# 06-multimodal-analogfrontend-PPG.net
KiCad netlist of a schematic drawn in Altium Designer
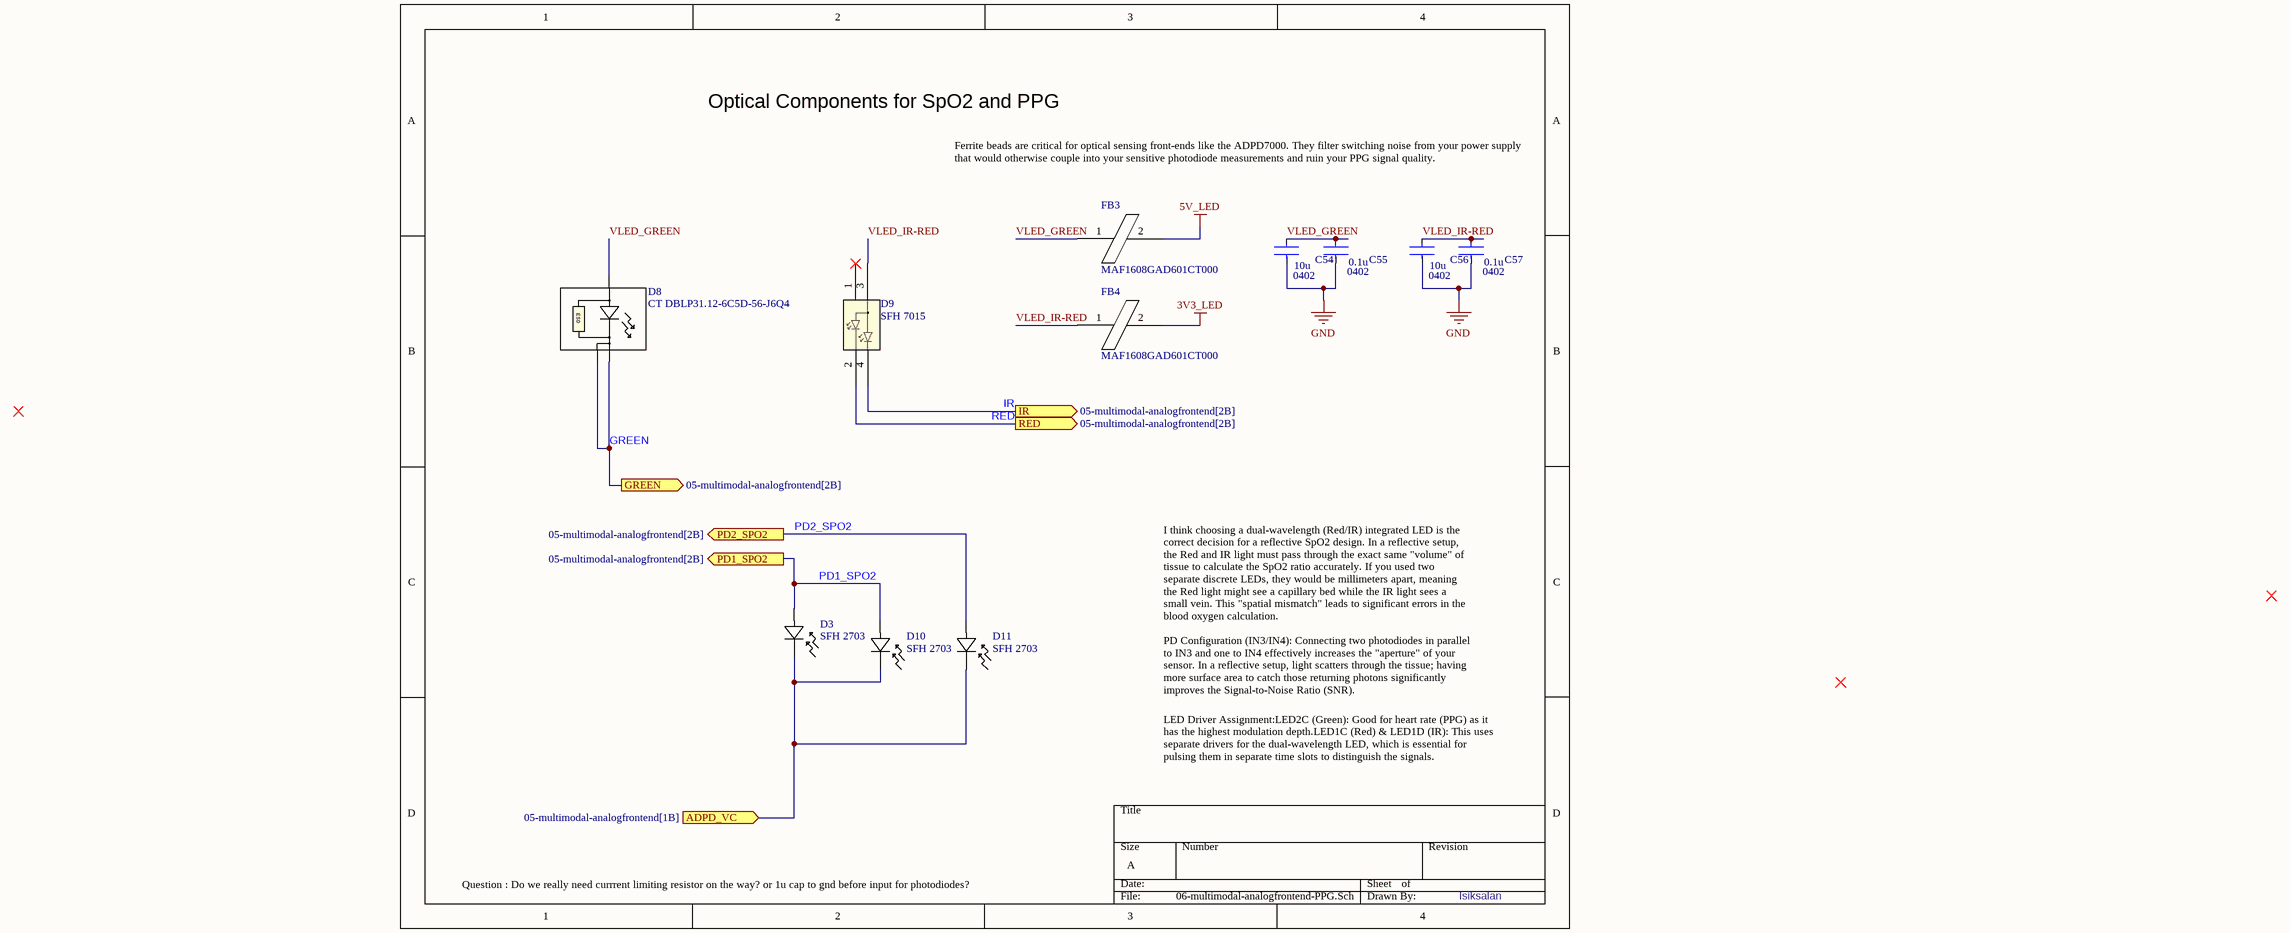
[diagram p0: 06-multimodal-analogfrontend-PPG.SchDoc]

(export (version "E")
  (design (tool "Eeschema 10.0.6"))
  (components
    (comp (ref "C54")
      (value "0402W106M6R3HI")
      (footprint "CAPTDK0402")
      (description "CAP SMD,0402,X5R,10UF,20%,6.3V")
      (libsource (lib "multimodal") (part "0402W106M6R3HI"))
    )
    (comp (ref "C55")
      (value "C1005X7R1H104K050BB")
      (footprint "CAPTDK0402")
      (description "CAP CER 0.1UF 50V X7R 0402")
      (libsource (lib "multimodal") (part "C1005X7R1H104K050BB"))
    )
    (comp (ref "C56")
      (value "0402W106M6R3HI")
      (footprint "CAPTDK0402")
      (description "CAP SMD,0402,X5R,10UF,20%,6.3V")
      (libsource (lib "multimodal") (part "0402W106M6R3HI"))
    )
    (comp (ref "C57")
      (value "C1005X7R1H104K050BB")
      (footprint "CAPTDK0402")
      (description "CAP CER 0.1UF 50V X7R 0402")
      (libsource (lib "multimodal") (part "C1005X7R1H104K050BB"))
    )
    (comp (ref "D3")
      (value "SFH 2703")
      (footprint "LED_SFH 2703_OSR")
      (description "SENSOR PHOTODIODE 940NM 2SMD")
      (fields (field (name "COPYRIGHT") "Copyright (C) 2025 Ultra Librarian. All rights reserved."))
      (libsource (lib "multimodal") (part "SFH 2703"))
    )
    (comp (ref "D8")
      (value "CT DBLP31.12-6C5D-56-J6Q4")
      (footprint "CT DBLP31.12-6C5D-56-J6Q4_OSR")
      (description "LED GREEN CLEAR SMD Green 536nm LED Indication - Discrete 2.3V 3-SMD, No Lead")
      (fields (field (name "COPYRIGHT") "Copyright (C) 2025 Ultra Librarian. All rights reserved."))
      (libsource (lib "multimodal") (part "CT DBLP31.12-6C5D-56-J6Q4"))
    )
    (comp (ref "D9")
      (value "SFH 7015")
      (footprint "SFH 7015_OSR")
      (description "Multi-Color LEDs Red / IR LED 655nm / 940nm")
      (fields (field (name "COPYRIGHT") "Copyright (C) 2026 Ultra Librarian. All rights reserved."))
      (libsource (lib "multimodal") (part "SFH 7015"))
    )
    (comp (ref "D10")
      (value "SFH 2703")
      (footprint "LED_SFH 2703_OSR")
      (description "SENSOR PHOTODIODE 940NM 2SMD")
      (fields (field (name "COPYRIGHT") "Copyright (C) 2025 Ultra Librarian. All rights reserved."))
      (libsource (lib "multimodal") (part "SFH 2703"))
    )
    (comp (ref "D11")
      (value "SFH 2703")
      (footprint "LED_SFH 2703_OSR")
      (description "SENSOR PHOTODIODE 940NM 2SMD")
      (fields (field (name "COPYRIGHT") "Copyright (C) 2025 Ultra Librarian. All rights reserved."))
      (libsource (lib "multimodal") (part "SFH 2703"))
    )
    (comp (ref "FB3")
      (value "MAF1608GAD601CT000")
      (footprint "INDMURT0603")
      (description "FERRITE BEAD 120 OHM 0603 1LN")
      (libsource (lib "multimodal") (part "MAF1608GAD601CT000"))
    )
    (comp (ref "FB4")
      (value "MAF1608GAD601CT000")
      (footprint "INDMURT0603")
      (description "FERRITE BEAD 120 OHM 0603 1LN")
      (libsource (lib "multimodal") (part "MAF1608GAD601CT000"))
    )
  )
  (nets
    (net (code "2") (name "/ADPD_VC") (class "Default")
      (node (ref "D10") (pin "1") (pinfunction "1_1") (pintype "passive"))
      (node (ref "D11") (pin "1") (pinfunction "1_1") (pintype "passive"))
      (node (ref "D3") (pin "1") (pinfunction "1_1") (pintype "passive"))
    )
    (net (code "3") (name "/GREEN") (class "Default")
      (node (ref "D8") (pin "1") (pinfunction "1_1") (pintype "passive"))
      (node (ref "D8") (pin "3") (pinfunction "3_3") (pintype "passive"))
    )
    (net (code "4") (name "/IR") (class "Default")
      (node (ref "D9") (pin "4") (pinfunction "4_4") (pintype "passive"))
    )
    (net (code "5") (name "/PD1_SPO2") (class "Default")
      (node (ref "D10") (pin "2") (pinfunction "2_2") (pintype "passive"))
      (node (ref "D3") (pin "2") (pinfunction "2_2") (pintype "passive"))
    )
    (net (code "6") (name "/PD2_SPO2") (class "Default")
      (node (ref "D11") (pin "2") (pinfunction "2_2") (pintype "passive"))
    )
    (net (code "7") (name "/RED") (class "Default")
      (node (ref "D9") (pin "2") (pinfunction "2_2") (pintype "passive"))
    )
    (net (code "8") (name "/VLED_GREEN") (class "Default")
      (node (ref "C54") (pin "1") (pinfunction "1_1") (pintype "passive"))
      (node (ref "C55") (pin "1") (pinfunction "1_1") (pintype "passive"))
      (node (ref "D8") (pin "2") (pinfunction "2_2") (pintype "passive"))
      (node (ref "FB3") (pin "1") (pinfunction "1_1") (pintype "passive"))
    )
    (net (code "9") (name "/VLED_IR-RED") (class "Default")
      (node (ref "C56") (pin "1") (pinfunction "1_1") (pintype "passive"))
      (node (ref "C57") (pin "1") (pinfunction "1_1") (pintype "passive"))
      (node (ref "D9") (pin "3") (pinfunction "3_3") (pintype "passive"))
      (node (ref "FB4") (pin "1") (pinfunction "1_1") (pintype "passive"))
    )
    (net (code "10") (name "3V3_LED") (class "Default")
      (node (ref "FB4") (pin "2") (pinfunction "2_2") (pintype "passive"))
    )
    (net (code "11") (name "5V_LED") (class "Default")
      (node (ref "FB3") (pin "2") (pinfunction "2_2") (pintype "passive"))
    )
    (net (code "12") (name "GND") (class "Default")
      (node (ref "C54") (pin "2") (pinfunction "2_2") (pintype "passive"))
      (node (ref "C55") (pin "2") (pinfunction "2_2") (pintype "passive"))
      (node (ref "C56") (pin "2") (pinfunction "2_2") (pintype "passive"))
      (node (ref "C57") (pin "2") (pinfunction "2_2") (pintype "passive"))
    )
    (net (code "13") (name "unconnected-(D9-Pad1)") (class "Default")
      (node (ref "D9") (pin "1") (pinfunction "1_1") (pintype "passive+no_connect"))
    )
  )
)
